# MainBoard_V1.net
KiCad netlist of a schematic drawn in EAGLE
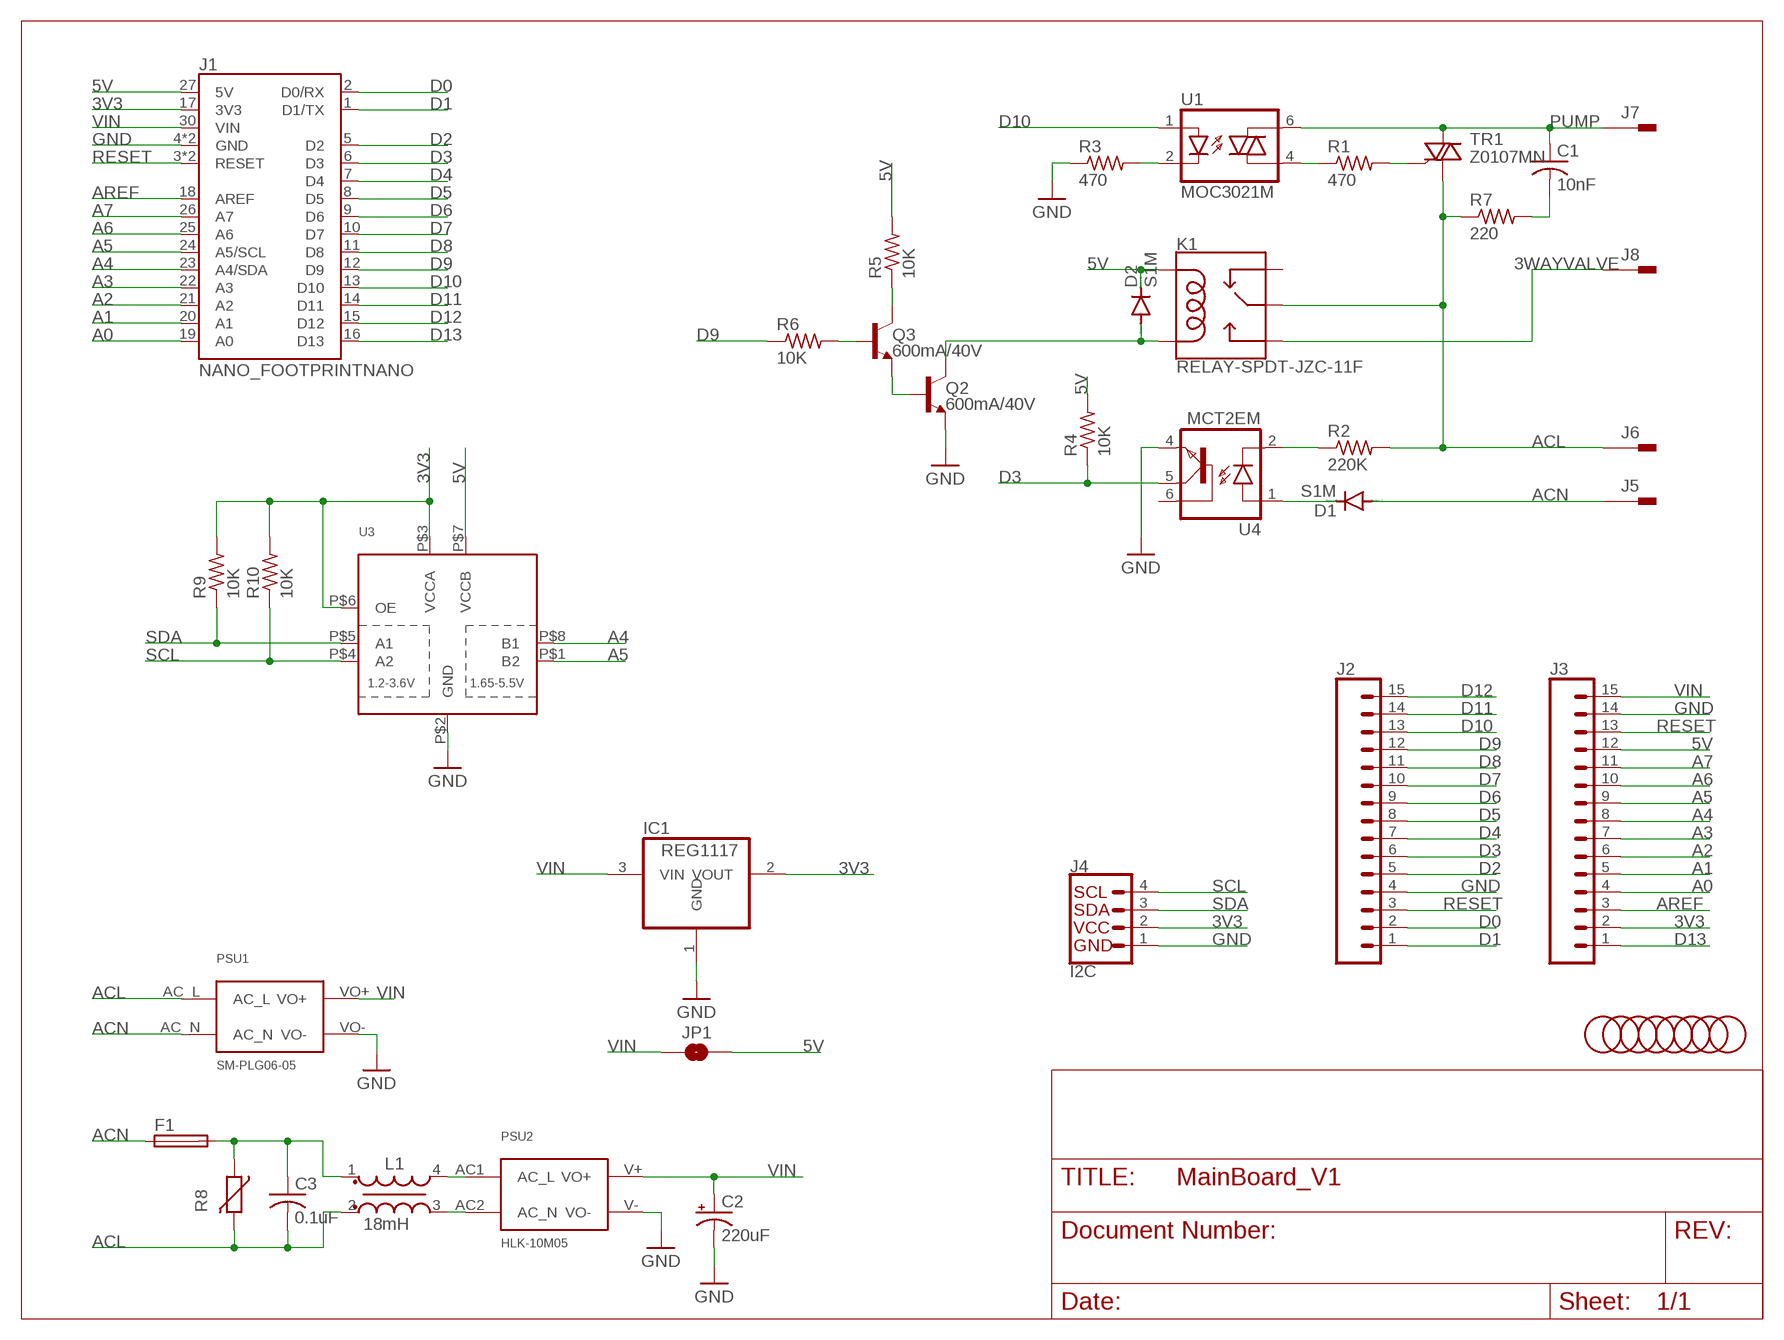
[diagram p0: schematic, sheet 1]

(export (version "E")
  (design (tool "Eeschema 10.0.6"))
  (components
    (comp (ref "C1")
      (value "10nF")
      (footprint "eagle-import:C075-032X103")
      (libsource (lib "eagle-import") (part "C-US075-032X103"))
    )
    (comp (ref "C2")
      (value "220uF")
      (footprint "eagle-import:E2,5-6")
      (libsource (lib "eagle-import") (part "CPOL-USE2.5-6"))
    )
    (comp (ref "C3")
      (value "0.1uF")
      (footprint "eagle-import:C150-054X183")
      (libsource (lib "eagle-import") (part "C-US150-054X183"))
    )
    (comp (ref "D1")
      (value "S1M")
      (footprint "eagle-import:SMA")
      (libsource (lib "eagle-import") (part "S1M"))
    )
    (comp (ref "D2")
      (value "S1M")
      (footprint "eagle-import:SMA")
      (libsource (lib "eagle-import") (part "S1M"))
    )
    (comp (ref "F1")
      (value "FUSETE5")
      (footprint "eagle-import:TE5")
      (libsource (lib "eagle-import") (part "FUSETE5"))
    )
    (comp (ref "IC1")
      (value "REG1117")
      (footprint "eagle-import:SOT223")
      (libsource (lib "eagle-import") (part "REG1117"))
    )
    (comp (ref "J1")
      (value "NANO_FOOTPRINTNANO")
      (footprint "eagle-import:NANO")
      (libsource (lib "eagle-import") (part "NANO_FOOTPRINTNANO"))
    )
    (comp (ref "J2")
      (value "CONN_15")
      (footprint "eagle-import:1X15")
      (libsource (lib "eagle-import") (part "CONN_15"))
    )
    (comp (ref "J3")
      (value "CONN_15")
      (footprint "eagle-import:1X15")
      (libsource (lib "eagle-import") (part "CONN_15"))
    )
    (comp (ref "J4")
      (value "I2C")
      (footprint "eagle-import:JST04_1MM_VERT")
      (libsource (lib "eagle-import") (part "QWIIC_CONNECTOR"))
    )
    (comp (ref "J5")
      (value "PIN262409-1")
      (footprint "eagle-import:62409-1")
      (libsource (lib "eagle-import") (part "PIN262409-1"))
    )
    (comp (ref "J6")
      (value "PIN262409-1")
      (footprint "eagle-import:62409-1")
      (libsource (lib "eagle-import") (part "PIN262409-1"))
    )
    (comp (ref "J7")
      (value "PIN262409-1")
      (footprint "eagle-import:62409-1")
      (libsource (lib "eagle-import") (part "PIN262409-1"))
    )
    (comp (ref "J8")
      (value "PIN262409-1")
      (footprint "eagle-import:62409-1")
      (libsource (lib "eagle-import") (part "PIN262409-1"))
    )
    (comp (ref "JP1")
      (value "JUMPER-SMT_2_NO_SILK")
      (footprint "eagle-import:SMT-JUMPER_2_NO_SILK")
      (libsource (lib "eagle-import") (part "JUMPER-SMT_2_NO_SILK"))
    )
    (comp (ref "K1")
      (value "RELAY-SPDT-JZC-11F")
      (footprint "eagle-import:RELAY-JZC")
      (libsource (lib "eagle-import") (part "RELAY-SPDT-JZC-11F"))
    )
    (comp (ref "L1")
      (value "18mH")
      (footprint "eagle-import:WE-TFC_UU9.8V")
      (libsource (lib "eagle-import") (part "WE-TFC_UU9.8V_744862180"))
    )
    (comp (ref "PSU1")
      (value "SM-PLG06-05")
      (footprint "eagle-import:SM-PLG06")
      (libsource (lib "eagle-import") (part "SM-PLG06-05"))
    )
    (comp (ref "PSU2")
      (value "HLK-10M05")
      (footprint "eagle-import:HLK-10MXX")
      (libsource (lib "eagle-import") (part "HLK-10M05"))
    )
    (comp (ref "Q2")
      (value "600mA/40V")
      (footprint "eagle-import:SOT23-3")
      (libsource (lib "eagle-import") (part "TRANS_NPN-MMBT2222AL"))
    )
    (comp (ref "Q3")
      (value "600mA/40V")
      (footprint "eagle-import:SOT23-3")
      (libsource (lib "eagle-import") (part "TRANS_NPN-MMBT2222AL"))
    )
    (comp (ref "R1")
      (value "470")
      (footprint "eagle-import:R0603")
      (libsource (lib "eagle-import") (part "R-US_R0603"))
    )
    (comp (ref "R2")
      (value "220K")
      (footprint "eagle-import:R0603")
      (libsource (lib "eagle-import") (part "R-US_R0603"))
    )
    (comp (ref "R3")
      (value "470")
      (footprint "eagle-import:R0603")
      (libsource (lib "eagle-import") (part "R-US_R0603"))
    )
    (comp (ref "R4")
      (value "10K")
      (footprint "eagle-import:R0603")
      (libsource (lib "eagle-import") (part "R-US_R0603"))
    )
    (comp (ref "R5")
      (value "10K")
      (footprint "eagle-import:R0603")
      (libsource (lib "eagle-import") (part "R-US_R0603"))
    )
    (comp (ref "R6")
      (value "10K")
      (footprint "eagle-import:R0603")
      (libsource (lib "eagle-import") (part "R-US_R0603"))
    )
    (comp (ref "R7")
      (value "220")
      (footprint "eagle-import:R2512")
      (libsource (lib "eagle-import") (part "R-US_R2512"))
    )
    (comp (ref "R8")
      (value "VARISTOR-7,5")
      (footprint "eagle-import:R-7,5")
      (libsource (lib "eagle-import") (part "VARISTOR-7,5"))
    )
    (comp (ref "R9")
      (value "10K")
      (footprint "eagle-import:R0603")
      (libsource (lib "eagle-import") (part "R-US_R0603"))
    )
    (comp (ref "R10")
      (value "10K")
      (footprint "eagle-import:R0603")
      (libsource (lib "eagle-import") (part "R-US_R0603"))
    )
    (comp (ref "TR1")
      (value "Z0107MN")
      (footprint "eagle-import:SOT223")
      (libsource (lib "eagle-import") (part "Z0107MNSOT-223"))
    )
    (comp (ref "U$1")
      (value "FIDUCIAL")
      (footprint "eagle-import:FIDUCIAL_1MM")
      (libsource (lib "eagle-import") (part "FIDUCIAL"))
    )
    (comp (ref "U$2")
      (value "FIDUCIAL")
      (footprint "eagle-import:FIDUCIAL_1MM")
      (libsource (lib "eagle-import") (part "FIDUCIAL"))
    )
    (comp (ref "U$3")
      (value "FIDUCIAL")
      (footprint "eagle-import:FIDUCIAL_1MM")
      (libsource (lib "eagle-import") (part "FIDUCIAL"))
    )
    (comp (ref "U$4")
      (value "FIDUCIAL")
      (footprint "eagle-import:FIDUCIAL_1MM")
      (libsource (lib "eagle-import") (part "FIDUCIAL"))
    )
    (comp (ref "U$5")
      (value "FIDUCIAL")
      (footprint "eagle-import:FIDUCIAL_1MM")
      (libsource (lib "eagle-import") (part "FIDUCIAL"))
    )
    (comp (ref "U$6")
      (value "FIDUCIAL")
      (footprint "eagle-import:FIDUCIAL_1MM")
      (libsource (lib "eagle-import") (part "FIDUCIAL"))
    )
    (comp (ref "U$7")
      (value "FIDUCIAL")
      (footprint "eagle-import:FIDUCIAL_1MM")
      (libsource (lib "eagle-import") (part "FIDUCIAL"))
    )
    (comp (ref "U$8")
      (value "FIDUCIAL")
      (footprint "eagle-import:FIDUCIAL_1MM")
      (libsource (lib "eagle-import") (part "FIDUCIAL"))
    )
    (comp (ref "U1")
      (value "MOC3021M")
      (footprint "eagle-import:DIL06")
      (libsource (lib "eagle-import") (part "MOC3021M"))
    )
    (comp (ref "U3")
      (value "TXS0102")
      (footprint "eagle-import:VFSOP-8")
      (libsource (lib "eagle-import") (part "TXS0102"))
    )
    (comp (ref "U4")
      (value "MCT2EM")
      (footprint "eagle-import:PDIP6_8P89X6P60_ONS")
      (fields (field (name "COPYRIGHT") "Copyright (C) 2021 Ultra Librarian. All rights reserved."))
      (libsource (lib "eagle-import") (part "MCT2EM"))
    )
  )
  (nets
    (net (code "1") (name "/3V3") (class "Default")
      (node (ref "IC1") (pin "2") (pinfunction "VOUT_2") (pintype "output"))
      (node (ref "J1") (pin "17") (pinfunction "3V3_17") (pintype "bidirectional"))
      (node (ref "J3") (pin "2") (pinfunction "2_2") (pintype "passive"))
      (node (ref "J4") (pin "2") (pinfunction "2_2") (pintype "power_in"))
      (node (ref "R10") (pin "2") (pinfunction "2_2") (pintype "passive"))
      (node (ref "R9") (pin "2") (pinfunction "2_2") (pintype "passive"))
      (node (ref "U3") (pin "P$3") (pinfunction "VCCA_P$3") (pintype "bidirectional"))
      (node (ref "U3") (pin "P$6") (pinfunction "OE_P$6") (pintype "bidirectional"))
    )
    (net (code "2") (name "/3WAYVALVE") (class "Default")
      (node (ref "J8") (pin "A1") (pinfunction "1_A1") (pintype "passive"))
      (node (ref "J8") (pin "A2") (pinfunction "1_A2") (pintype "passive"))
      (node (ref "K1") (pin "3") (pinfunction "NO_3") (pintype "bidirectional"))
    )
    (net (code "3") (name "/5V") (class "Default")
      (node (ref "D2") (pin "C") (pinfunction "C_C") (pintype "passive"))
      (node (ref "J1") (pin "27") (pinfunction "5V_27") (pintype "bidirectional"))
      (node (ref "J3") (pin "12") (pinfunction "12_12") (pintype "passive"))
      (node (ref "JP1") (pin "2") (pinfunction "2_2") (pintype "passive"))
      (node (ref "K1") (pin "5") (pinfunction "COIL1_5") (pintype "bidirectional"))
      (node (ref "R4") (pin "2") (pinfunction "2_2") (pintype "passive"))
      (node (ref "R5") (pin "2") (pinfunction "2_2") (pintype "passive"))
      (node (ref "U3") (pin "P$7") (pinfunction "VCCB_P$7") (pintype "bidirectional"))
    )
    (net (code "4") (name "/A0") (class "Default")
      (node (ref "J1") (pin "19") (pinfunction "A0_19") (pintype "bidirectional"))
      (node (ref "J3") (pin "4") (pinfunction "4_4") (pintype "passive"))
    )
    (net (code "5") (name "/A1") (class "Default")
      (node (ref "J1") (pin "20") (pinfunction "A1_20") (pintype "bidirectional"))
      (node (ref "J3") (pin "5") (pinfunction "5_5") (pintype "passive"))
    )
    (net (code "6") (name "/A2") (class "Default")
      (node (ref "J1") (pin "21") (pinfunction "A2_21") (pintype "bidirectional"))
      (node (ref "J3") (pin "6") (pinfunction "6_6") (pintype "passive"))
    )
    (net (code "7") (name "/A3") (class "Default")
      (node (ref "J1") (pin "22") (pinfunction "A3_22") (pintype "bidirectional"))
      (node (ref "J3") (pin "7") (pinfunction "7_7") (pintype "passive"))
    )
    (net (code "8") (name "/A4") (class "Default")
      (node (ref "J1") (pin "23") (pinfunction "A4/SDA_23") (pintype "bidirectional"))
      (node (ref "J3") (pin "8") (pinfunction "8_8") (pintype "passive"))
      (node (ref "U3") (pin "P$8") (pinfunction "B1_P$8") (pintype "bidirectional"))
    )
    (net (code "9") (name "/A5") (class "Default")
      (node (ref "J1") (pin "24") (pinfunction "A5/SCL_24") (pintype "bidirectional"))
      (node (ref "J3") (pin "9") (pinfunction "9_9") (pintype "passive"))
      (node (ref "U3") (pin "P$1") (pinfunction "B2_P$1") (pintype "bidirectional"))
    )
    (net (code "10") (name "/A6") (class "Default")
      (node (ref "J1") (pin "25") (pinfunction "A6_25") (pintype "bidirectional"))
      (node (ref "J3") (pin "10") (pinfunction "10_10") (pintype "passive"))
    )
    (net (code "11") (name "/A7") (class "Default")
      (node (ref "J1") (pin "26") (pinfunction "A7_26") (pintype "bidirectional"))
      (node (ref "J3") (pin "11") (pinfunction "11_11") (pintype "passive"))
    )
    (net (code "12") (name "/ACL") (class "Default")
      (node (ref "C3") (pin "2") (pinfunction "2_2") (pintype "passive"))
      (node (ref "J6") (pin "A1") (pinfunction "1_A1") (pintype "passive"))
      (node (ref "J6") (pin "A2") (pinfunction "1_A2") (pintype "passive"))
      (node (ref "K1") (pin "4") (pinfunction "MAIN_4") (pintype "bidirectional"))
      (node (ref "L1") (pin "2") (pinfunction "2_2") (pintype "passive"))
      (node (ref "PSU1") (pin "AC_L") (pinfunction "AC_L_AC_L") (pintype "bidirectional"))
      (node (ref "R2") (pin "2") (pinfunction "2_2") (pintype "passive"))
      (node (ref "R7") (pin "1") (pinfunction "1_1") (pintype "passive"))
      (node (ref "R8") (pin "2") (pinfunction "2_2") (pintype "passive"))
      (node (ref "TR1") (pin "1") (pinfunction "A1_1") (pintype "passive"))
    )
    (net (code "13") (name "/ACN") (class "Default")
      (node (ref "D1") (pin "A") (pinfunction "A_A") (pintype "passive"))
      (node (ref "F1") (pin "1") (pinfunction "1_1") (pintype "passive"))
      (node (ref "J5") (pin "A1") (pinfunction "1_A1") (pintype "passive"))
      (node (ref "J5") (pin "A2") (pinfunction "1_A2") (pintype "passive"))
      (node (ref "PSU1") (pin "AC_N") (pinfunction "AC_N_AC_N") (pintype "bidirectional"))
    )
    (net (code "14") (name "/AREF") (class "Default")
      (node (ref "J1") (pin "18") (pinfunction "AREF_18") (pintype "bidirectional"))
      (node (ref "J3") (pin "3") (pinfunction "3_3") (pintype "passive"))
    )
    (net (code "15") (name "/D0") (class "Default")
      (node (ref "J1") (pin "2") (pinfunction "D0/RX_2") (pintype "bidirectional"))
      (node (ref "J2") (pin "2") (pinfunction "2_2") (pintype "passive"))
    )
    (net (code "16") (name "/D1") (class "Default")
      (node (ref "J1") (pin "1") (pinfunction "D1/TX_1") (pintype "bidirectional"))
      (node (ref "J2") (pin "1") (pinfunction "1_1") (pintype "passive"))
    )
    (net (code "17") (name "/D2") (class "Default")
      (node (ref "J1") (pin "5") (pinfunction "D2_5") (pintype "bidirectional"))
      (node (ref "J2") (pin "5") (pinfunction "5_5") (pintype "passive"))
    )
    (net (code "18") (name "/D3") (class "Default")
      (node (ref "J1") (pin "6") (pinfunction "D3_6") (pintype "bidirectional"))
      (node (ref "J2") (pin "6") (pinfunction "6_6") (pintype "passive"))
      (node (ref "R4") (pin "1") (pinfunction "1_1") (pintype "passive"))
      (node (ref "U4") (pin "5") (pinfunction "COL_5") (pintype "passive"))
    )
    (net (code "19") (name "/D4") (class "Default")
      (node (ref "J1") (pin "7") (pinfunction "D4_7") (pintype "bidirectional"))
      (node (ref "J2") (pin "7") (pinfunction "7_7") (pintype "passive"))
    )
    (net (code "20") (name "/D5") (class "Default")
      (node (ref "J1") (pin "8") (pinfunction "D5_8") (pintype "bidirectional"))
      (node (ref "J2") (pin "8") (pinfunction "8_8") (pintype "passive"))
    )
    (net (code "21") (name "/D6") (class "Default")
      (node (ref "J1") (pin "9") (pinfunction "D6_9") (pintype "bidirectional"))
      (node (ref "J2") (pin "9") (pinfunction "9_9") (pintype "passive"))
    )
    (net (code "22") (name "/D7") (class "Default")
      (node (ref "J1") (pin "10") (pinfunction "D7_10") (pintype "bidirectional"))
      (node (ref "J2") (pin "10") (pinfunction "10_10") (pintype "passive"))
    )
    (net (code "23") (name "/D8") (class "Default")
      (node (ref "J1") (pin "11") (pinfunction "D8_11") (pintype "bidirectional"))
      (node (ref "J2") (pin "11") (pinfunction "11_11") (pintype "passive"))
    )
    (net (code "24") (name "/D9") (class "Default")
      (node (ref "J1") (pin "12") (pinfunction "D9_12") (pintype "bidirectional"))
      (node (ref "J2") (pin "12") (pinfunction "12_12") (pintype "passive"))
      (node (ref "R6") (pin "1") (pinfunction "1_1") (pintype "passive"))
    )
    (net (code "25") (name "/D10") (class "Default")
      (node (ref "J1") (pin "13") (pinfunction "D10_13") (pintype "bidirectional"))
      (node (ref "J2") (pin "13") (pinfunction "13_13") (pintype "passive"))
      (node (ref "U1") (pin "1") (pinfunction "A_1") (pintype "passive"))
    )
    (net (code "26") (name "/D11") (class "Default")
      (node (ref "J1") (pin "14") (pinfunction "D11_14") (pintype "bidirectional"))
      (node (ref "J2") (pin "14") (pinfunction "14_14") (pintype "passive"))
    )
    (net (code "27") (name "/D12") (class "Default")
      (node (ref "J1") (pin "15") (pinfunction "D12_15") (pintype "bidirectional"))
      (node (ref "J2") (pin "15") (pinfunction "15_15") (pintype "passive"))
    )
    (net (code "28") (name "/D13") (class "Default")
      (node (ref "J1") (pin "16") (pinfunction "D13_16") (pintype "bidirectional"))
      (node (ref "J3") (pin "1") (pinfunction "1_1") (pintype "passive"))
    )
    (net (code "29") (name "/PUMP") (class "Default")
      (node (ref "C1") (pin "1") (pinfunction "1_1") (pintype "passive"))
      (node (ref "J7") (pin "A1") (pinfunction "1_A1") (pintype "passive"))
      (node (ref "J7") (pin "A2") (pinfunction "1_A2") (pintype "passive"))
      (node (ref "TR1") (pin "2") (pinfunction "A2_2") (pintype "passive"))
      (node (ref "TR1") (pin "4") (pinfunction "A2_4") (pintype "passive"))
      (node (ref "U1") (pin "6") (pinfunction "A2_6") (pintype "passive"))
    )
    (net (code "30") (name "/RESET") (class "Default")
      (node (ref "J1") (pin "28") (pinfunction "RESET_28") (pintype "bidirectional"))
      (node (ref "J1") (pin "3") (pinfunction "RESET_3") (pintype "bidirectional"))
      (node (ref "J2") (pin "3") (pinfunction "3_3") (pintype "passive"))
      (node (ref "J3") (pin "13") (pinfunction "13_13") (pintype "passive"))
    )
    (net (code "31") (name "/SCL") (class "Default")
      (node (ref "J4") (pin "4") (pinfunction "4_4") (pintype "passive"))
      (node (ref "R10") (pin "1") (pinfunction "1_1") (pintype "passive"))
      (node (ref "U3") (pin "P$4") (pinfunction "A2_P$4") (pintype "bidirectional"))
    )
    (net (code "32") (name "/SDA") (class "Default")
      (node (ref "J4") (pin "3") (pinfunction "3_3") (pintype "passive"))
      (node (ref "R9") (pin "1") (pinfunction "1_1") (pintype "passive"))
      (node (ref "U3") (pin "P$5") (pinfunction "A1_P$5") (pintype "bidirectional"))
    )
    (net (code "33") (name "/VIN") (class "Default")
      (node (ref "C2") (pin "+") (pinfunction "+_+") (pintype "passive"))
      (node (ref "IC1") (pin "3") (pinfunction "VIN_3") (pintype "input"))
      (node (ref "J1") (pin "30") (pinfunction "VIN_30") (pintype "bidirectional"))
      (node (ref "J3") (pin "15") (pinfunction "15_15") (pintype "passive"))
      (node (ref "JP1") (pin "1") (pinfunction "1_1") (pintype "passive"))
      (node (ref "PSU1") (pin "VO+") (pinfunction "VO+_VO+") (pintype "bidirectional"))
      (node (ref "PSU2") (pin "V+") (pinfunction "VO+_V+") (pintype "bidirectional"))
    )
    (net (code "34") (name "GND") (class "Default")
      (node (ref "C2") (pin "-") (pinfunction "-_-") (pintype "passive"))
      (node (ref "IC1") (pin "1") (pinfunction "GND_1") (pintype "power_in"))
      (node (ref "J1") (pin "29") (pinfunction "GND_29") (pintype "bidirectional"))
      (node (ref "J1") (pin "4") (pinfunction "GND_4") (pintype "bidirectional"))
      (node (ref "J2") (pin "4") (pinfunction "4_4") (pintype "passive"))
      (node (ref "J3") (pin "14") (pinfunction "14_14") (pintype "passive"))
      (node (ref "J4") (pin "1") (pinfunction "1_1") (pintype "power_in"))
      (node (ref "PSU1") (pin "VO-") (pinfunction "VO-_VO-") (pintype "bidirectional"))
      (node (ref "PSU2") (pin "V-") (pinfunction "VO-_V-") (pintype "bidirectional"))
      (node (ref "Q2") (pin "2") (pinfunction "E_2") (pintype "passive"))
      (node (ref "R3") (pin "1") (pinfunction "1_1") (pintype "passive"))
      (node (ref "U3") (pin "P$2") (pinfunction "GND_P$2") (pintype "bidirectional"))
      (node (ref "U4") (pin "4") (pinfunction "EMI_4") (pintype "passive"))
    )
    (net (code "35") (name "Net-(C1-Pad2)") (class "Default")
      (node (ref "C1") (pin "2") (pinfunction "2_2") (pintype "passive"))
      (node (ref "R7") (pin "2") (pinfunction "2_2") (pintype "passive"))
    )
    (net (code "36") (name "Net-(C3-Pad1)") (class "Default")
      (node (ref "C3") (pin "1") (pinfunction "1_1") (pintype "passive"))
      (node (ref "F1") (pin "2") (pinfunction "2_2") (pintype "passive"))
      (node (ref "L1") (pin "1") (pinfunction "1_1") (pintype "passive"))
      (node (ref "R8") (pin "1") (pinfunction "1_1") (pintype "passive"))
    )
    (net (code "37") (name "Net-(K1-COIL2)") (class "Default")
      (node (ref "D2") (pin "A") (pinfunction "A_A") (pintype "passive"))
      (node (ref "K1") (pin "1") (pinfunction "COIL2_1") (pintype "bidirectional"))
      (node (ref "Q2") (pin "3") (pinfunction "C_3") (pintype "passive"))
    )
    (net (code "38") (name "Net-(PSU2-AC_L)") (class "Default")
      (node (ref "L1") (pin "4") (pinfunction "4_4") (pintype "passive"))
      (node (ref "PSU2") (pin "AC1") (pinfunction "AC_L_AC1") (pintype "bidirectional"))
    )
    (net (code "39") (name "Net-(PSU2-AC_N)") (class "Default")
      (node (ref "L1") (pin "3") (pinfunction "3_3") (pintype "passive"))
      (node (ref "PSU2") (pin "AC2") (pinfunction "AC_N_AC2") (pintype "bidirectional"))
    )
    (net (code "40") (name "Net-(Q2-B)") (class "Default")
      (node (ref "Q2") (pin "1") (pinfunction "B_1") (pintype "passive"))
      (node (ref "Q3") (pin "2") (pinfunction "E_2") (pintype "passive"))
    )
    (net (code "41") (name "Net-(Q3-B)") (class "Default")
      (node (ref "Q3") (pin "1") (pinfunction "B_1") (pintype "passive"))
      (node (ref "R6") (pin "2") (pinfunction "2_2") (pintype "passive"))
    )
    (net (code "42") (name "Net-(Q3-C)") (class "Default")
      (node (ref "Q3") (pin "3") (pinfunction "C_3") (pintype "passive"))
      (node (ref "R5") (pin "1") (pinfunction "1_1") (pintype "passive"))
    )
    (net (code "43") (name "Net-(TR1-G)") (class "Default")
      (node (ref "R1") (pin "2") (pinfunction "2_2") (pintype "passive"))
      (node (ref "TR1") (pin "3") (pinfunction "G_3") (pintype "passive"))
    )
    (net (code "44") (name "Net-(U1-A1)") (class "Default")
      (node (ref "R1") (pin "1") (pinfunction "1_1") (pintype "passive"))
      (node (ref "U1") (pin "4") (pinfunction "A1_4") (pintype "passive"))
    )
    (net (code "45") (name "Net-(U1-C)") (class "Default")
      (node (ref "R3") (pin "2") (pinfunction "2_2") (pintype "passive"))
      (node (ref "U1") (pin "2") (pinfunction "C_2") (pintype "passive"))
    )
    (net (code "46") (name "Net-(U4-A)") (class "Default")
      (node (ref "D1") (pin "C") (pinfunction "C_C") (pintype "passive"))
      (node (ref "U4") (pin "1") (pinfunction "A_1") (pintype "passive"))
    )
    (net (code "47") (name "Net-(U4-C)") (class "Default")
      (node (ref "R2") (pin "1") (pinfunction "1_1") (pintype "passive"))
      (node (ref "U4") (pin "2") (pinfunction "C_2") (pintype "passive"))
    )
    (net (code "48") (name "unconnected-(K1-NC-Pad2)") (class "Default")
      (node (ref "K1") (pin "2") (pinfunction "NC_2") (pintype "bidirectional"))
    )
    (net (code "49") (name "unconnected-(U4-BAS-Pad6)") (class "Default")
      (node (ref "U4") (pin "6") (pinfunction "BAS_6") (pintype "passive"))
    )
  )
)
